# pc_pulse.net
KiCad netlist of a schematic drawn in EAGLE
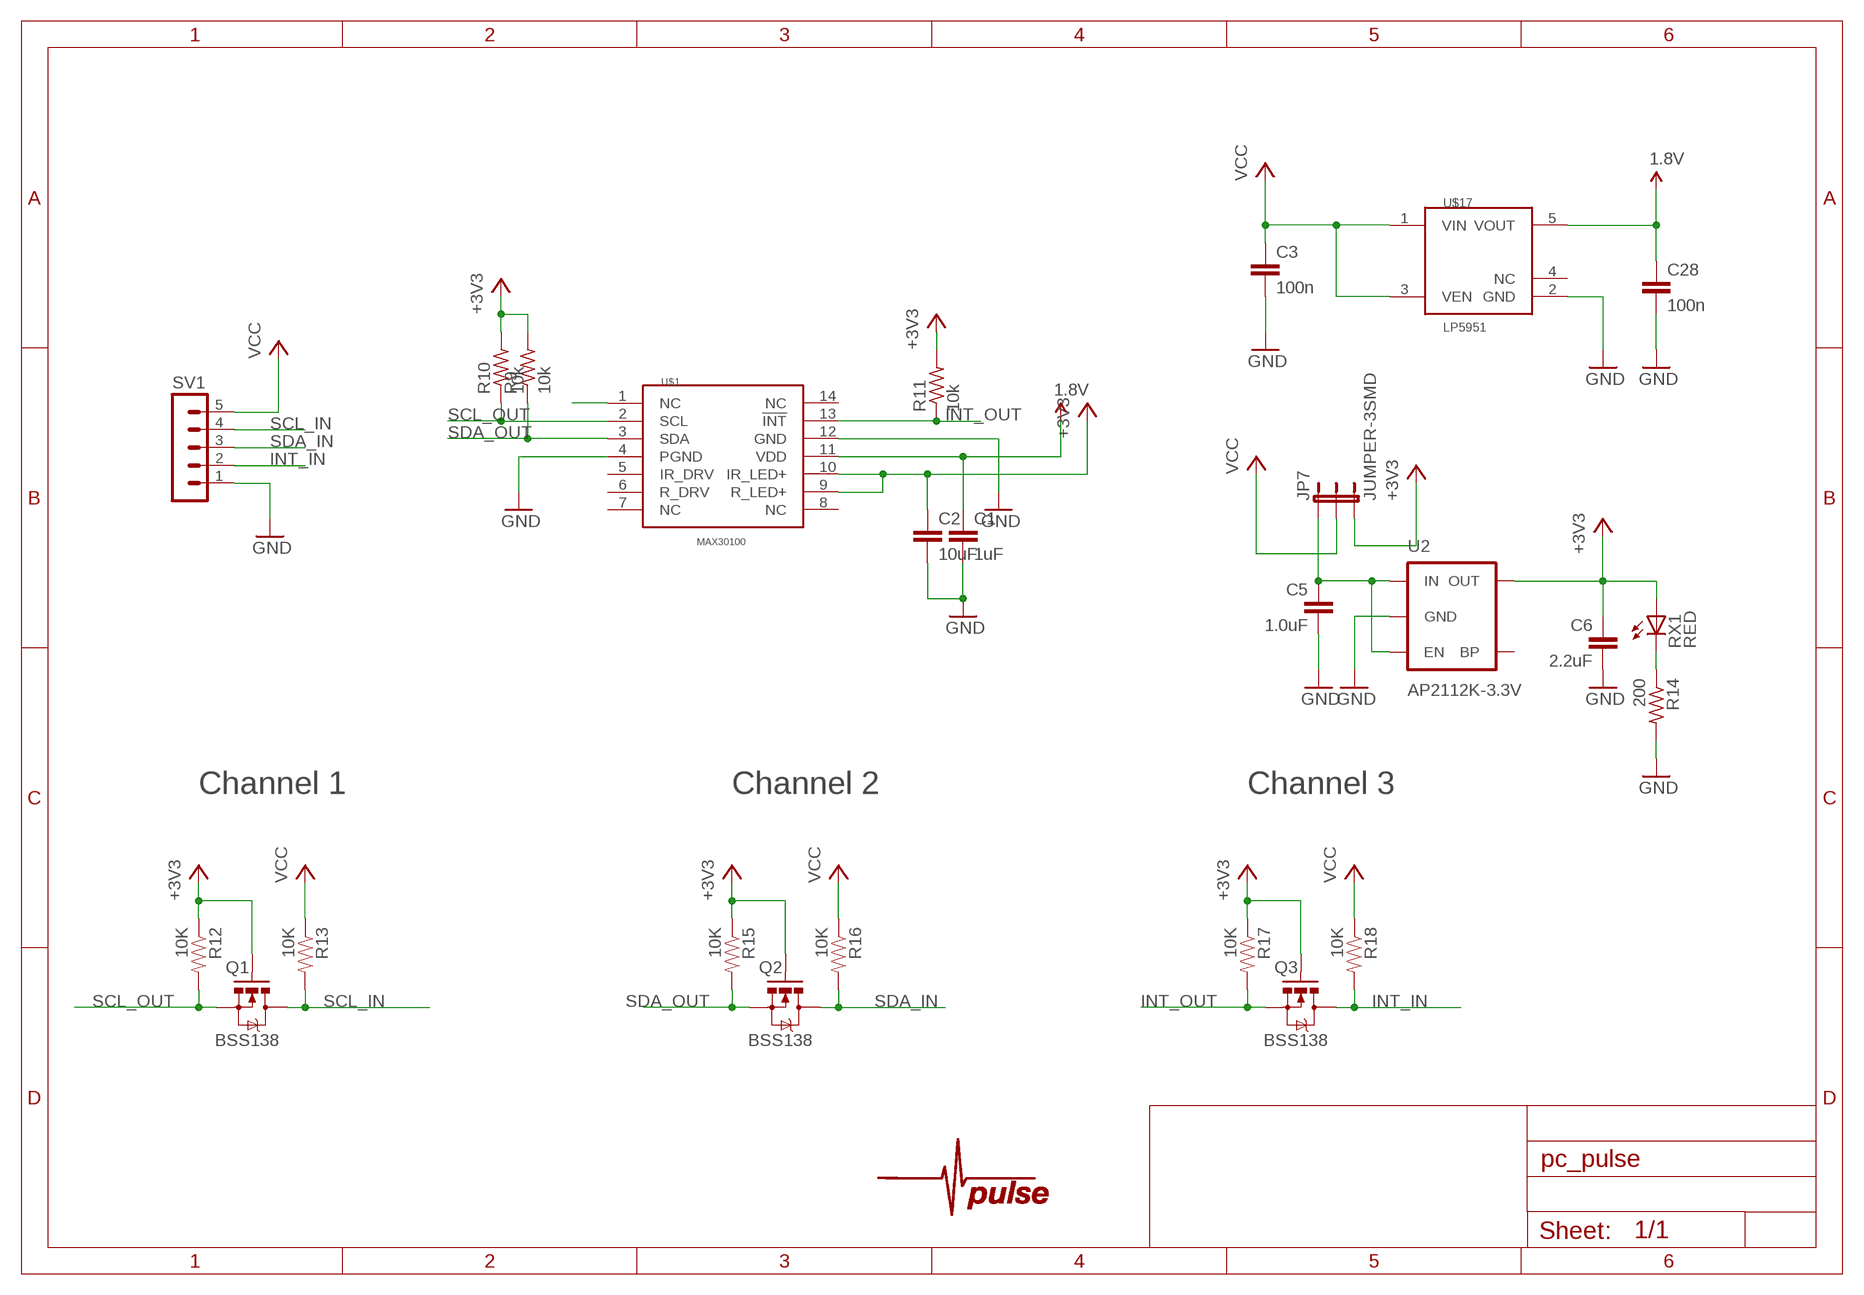
[diagram p0: schematic, sheet 1]

(export (version "E")
  (design (tool "Eeschema 10.0.6"))
  (components
    (comp (ref "C1")
      (value "1uF")
      (footprint "eagle-import:C0805")
      (libsource (lib "eagle-import") (part "C-EUC0805"))
    )
    (comp (ref "C2")
      (value "10uF")
      (footprint "eagle-import:C0805")
      (libsource (lib "eagle-import") (part "C-EUC0805"))
    )
    (comp (ref "C3")
      (value "100n")
      (footprint "eagle-import:C0402")
      (libsource (lib "eagle-import") (part "C-EUC0402"))
    )
    (comp (ref "C5")
      (value "1.0uF")
      (footprint "eagle-import:0805")
      (libsource (lib "eagle-import") (part "1.0UF-25V-+80/-20(0805)"))
    )
    (comp (ref "C6")
      (value "2.2uF")
      (footprint "eagle-import:C0805")
      (libsource (lib "eagle-import") (part "C-EUC0805"))
    )
    (comp (ref "C28")
      (value "100n")
      (footprint "eagle-import:C0402")
      (libsource (lib "eagle-import") (part "C-EUC0402"))
    )
    (comp (ref "JP7")
      (value "JUMPER-3SMD")
      (footprint "eagle-import:SJ_3")
      (libsource (lib "eagle-import") (part "JUMPER-3SMD"))
    )
    (comp (ref "Q1")
      (value "BSS138")
      (footprint "eagle-import:SOT23-3")
      (libsource (lib "eagle-import") (part "MOSFET-NCHANNELSMD"))
    )
    (comp (ref "Q2")
      (value "BSS138")
      (footprint "eagle-import:SOT23-3")
      (libsource (lib "eagle-import") (part "MOSFET-NCHANNELSMD"))
    )
    (comp (ref "Q3")
      (value "BSS138")
      (footprint "eagle-import:SOT23-3")
      (libsource (lib "eagle-import") (part "MOSFET-NCHANNELSMD"))
    )
    (comp (ref "R9")
      (value "10k")
      (footprint "eagle-import:R0402")
      (libsource (lib "eagle-import") (part "R-US_R0402"))
    )
    (comp (ref "R10")
      (value "10k")
      (footprint "eagle-import:R0402")
      (libsource (lib "eagle-import") (part "R-US_R0402"))
    )
    (comp (ref "R11")
      (value "10k")
      (footprint "eagle-import:R0402")
      (libsource (lib "eagle-import") (part "R-US_R0402"))
    )
    (comp (ref "R12")
      (value "10K")
      (footprint "eagle-import:0402-RES")
      (libsource (lib "eagle-import") (part "RESISTOR0402-RES"))
    )
    (comp (ref "R13")
      (value "10K")
      (footprint "eagle-import:0402-RES")
      (libsource (lib "eagle-import") (part "RESISTOR0402-RES"))
    )
    (comp (ref "R14")
      (value "200")
      (footprint "eagle-import:R0402")
      (libsource (lib "eagle-import") (part "R-US_R0402"))
    )
    (comp (ref "R15")
      (value "10K")
      (footprint "eagle-import:0402-RES")
      (libsource (lib "eagle-import") (part "RESISTOR0402-RES"))
    )
    (comp (ref "R16")
      (value "10K")
      (footprint "eagle-import:0402-RES")
      (libsource (lib "eagle-import") (part "RESISTOR0402-RES"))
    )
    (comp (ref "R17")
      (value "10K")
      (footprint "eagle-import:0402-RES")
      (libsource (lib "eagle-import") (part "RESISTOR0402-RES"))
    )
    (comp (ref "R18")
      (value "10K")
      (footprint "eagle-import:0402-RES")
      (libsource (lib "eagle-import") (part "RESISTOR0402-RES"))
    )
    (comp (ref "RX1")
      (value "RED")
      (footprint "eagle-import:CHIPLED_0603")
      (libsource (lib "eagle-import") (part "LEDCHIPLED_0603"))
    )
    (comp (ref "SV1")
      (value "MA05-1")
      (footprint "eagle-import:MA05-1")
      (libsource (lib "eagle-import") (part "MA05-1"))
    )
    (comp (ref "U$1")
      (value "MAX30100")
      (footprint "eagle-import:OESIP-14")
      (libsource (lib "eagle-import") (part "MAX30100"))
    )
    (comp (ref "U$3")
      (value "PROTY_LOGO_WITH_TEXT")
      (footprint "eagle-import:PROTY_WITH_TEXT")
      (libsource (lib "eagle-import") (part "PROTY_LOGO_WITH_TEXT"))
    )
    (comp (ref "U$4")
      (value "PULSE")
      (footprint "eagle-import:PULSE")
      (libsource (lib "eagle-import") (part "PULSE"))
    )
    (comp (ref "U$17")
      (value "LP5951")
      (footprint "eagle-import:SC70-5")
      (libsource (lib "eagle-import") (part "LP5951"))
    )
    (comp (ref "U2")
      (value "AP2112K-3.3V")
      (footprint "eagle-import:SOT23-5")
      (libsource (lib "eagle-import") (part "V_REG_LDOSMD"))
    )
  )
  (nets
    (net (code "1") (name "+3V3") (class "Default")
      (node (ref "C2") (pin "1") (pinfunction "1_1") (pintype "passive"))
      (node (ref "C6") (pin "1") (pinfunction "1_1") (pintype "passive"))
      (node (ref "JP7") (pin "3") (pinfunction "3_3") (pintype "passive"))
      (node (ref "Q1") (pin "1") (pinfunction "G_1") (pintype "passive"))
      (node (ref "Q2") (pin "1") (pinfunction "G_1") (pintype "passive"))
      (node (ref "Q3") (pin "1") (pinfunction "G_1") (pintype "passive"))
      (node (ref "R10") (pin "2") (pinfunction "2_2") (pintype "passive"))
      (node (ref "R11") (pin "2") (pinfunction "2_2") (pintype "passive"))
      (node (ref "R12") (pin "1") (pinfunction "1_1") (pintype "passive"))
      (node (ref "R15") (pin "1") (pinfunction "1_1") (pintype "passive"))
      (node (ref "R17") (pin "1") (pinfunction "1_1") (pintype "passive"))
      (node (ref "R9") (pin "2") (pinfunction "2_2") (pintype "passive"))
      (node (ref "RX1") (pin "A") (pinfunction "A_A") (pintype "passive"))
      (node (ref "U$1") (pin "10") (pinfunction "IR_LED+_10") (pintype "bidirectional"))
      (node (ref "U$1") (pin "9") (pinfunction "R_LED+_9") (pintype "bidirectional"))
      (node (ref "U2") (pin "5") (pinfunction "OUT_5") (pintype "passive"))
    )
    (net (code "2") (name "/INT_IN") (class "Default")
      (node (ref "Q3") (pin "3") (pinfunction "D_3") (pintype "passive"))
      (node (ref "R18") (pin "2") (pinfunction "2_2") (pintype "passive"))
      (node (ref "SV1") (pin "2") (pinfunction "2_2") (pintype "passive"))
    )
    (net (code "3") (name "/INT_OUT") (class "Default")
      (node (ref "Q3") (pin "2") (pinfunction "S_2") (pintype "passive"))
      (node (ref "R11") (pin "1") (pinfunction "1_1") (pintype "passive"))
      (node (ref "R17") (pin "2") (pinfunction "2_2") (pintype "passive"))
      (node (ref "U$1") (pin "13") (pinfunction "~{INT}_13") (pintype "bidirectional"))
    )
    (net (code "4") (name "/SCL_IN") (class "Default")
      (node (ref "Q1") (pin "3") (pinfunction "D_3") (pintype "passive"))
      (node (ref "R13") (pin "2") (pinfunction "2_2") (pintype "passive"))
      (node (ref "SV1") (pin "4") (pinfunction "4_4") (pintype "passive"))
    )
    (net (code "5") (name "/SCL_OUT") (class "Default")
      (node (ref "Q1") (pin "2") (pinfunction "S_2") (pintype "passive"))
      (node (ref "R10") (pin "1") (pinfunction "1_1") (pintype "passive"))
      (node (ref "R12") (pin "2") (pinfunction "2_2") (pintype "passive"))
      (node (ref "U$1") (pin "2") (pinfunction "SCL_2") (pintype "bidirectional"))
    )
    (net (code "6") (name "/SDA_IN") (class "Default")
      (node (ref "Q2") (pin "3") (pinfunction "D_3") (pintype "passive"))
      (node (ref "R16") (pin "2") (pinfunction "2_2") (pintype "passive"))
      (node (ref "SV1") (pin "3") (pinfunction "3_3") (pintype "passive"))
    )
    (net (code "7") (name "/SDA_OUT") (class "Default")
      (node (ref "Q2") (pin "2") (pinfunction "S_2") (pintype "passive"))
      (node (ref "R15") (pin "2") (pinfunction "2_2") (pintype "passive"))
      (node (ref "R9") (pin "1") (pinfunction "1_1") (pintype "passive"))
      (node (ref "U$1") (pin "3") (pinfunction "SDA_3") (pintype "bidirectional"))
    )
    (net (code "8") (name "1.8V") (class "Default")
      (node (ref "C1") (pin "1") (pinfunction "1_1") (pintype "passive"))
      (node (ref "C28") (pin "1") (pinfunction "1_1") (pintype "passive"))
      (node (ref "U$1") (pin "11") (pinfunction "VDD_11") (pintype "bidirectional"))
      (node (ref "U$17") (pin "5") (pinfunction "VOUT_5") (pintype "bidirectional"))
    )
    (net (code "9") (name "GND") (class "Default")
      (node (ref "C1") (pin "2") (pinfunction "2_2") (pintype "passive"))
      (node (ref "C2") (pin "2") (pinfunction "2_2") (pintype "passive"))
      (node (ref "C28") (pin "2") (pinfunction "2_2") (pintype "passive"))
      (node (ref "C3") (pin "2") (pinfunction "2_2") (pintype "passive"))
      (node (ref "C5") (pin "2") (pinfunction "2_2") (pintype "passive"))
      (node (ref "C6") (pin "2") (pinfunction "2_2") (pintype "passive"))
      (node (ref "R14") (pin "2") (pinfunction "2_2") (pintype "passive"))
      (node (ref "SV1") (pin "1") (pinfunction "1_1") (pintype "passive"))
      (node (ref "U$1") (pin "12") (pinfunction "GND_12") (pintype "bidirectional"))
      (node (ref "U$1") (pin "4") (pinfunction "PGND_4") (pintype "bidirectional"))
      (node (ref "U$17") (pin "2") (pinfunction "GND_2") (pintype "bidirectional"))
      (node (ref "U2") (pin "2") (pinfunction "GND_2") (pintype "input"))
    )
    (net (code "10") (name "Net-(R14-Pad1)") (class "Default")
      (node (ref "R14") (pin "1") (pinfunction "1_1") (pintype "passive"))
      (node (ref "RX1") (pin "C") (pinfunction "C_C") (pintype "passive"))
    )
    (net (code "11") (name "Net-(U2-EN)") (class "Default")
      (node (ref "C5") (pin "1") (pinfunction "1_1") (pintype "passive"))
      (node (ref "JP7") (pin "1") (pinfunction "1_1") (pintype "passive"))
      (node (ref "U2") (pin "1") (pinfunction "IN_1") (pintype "input"))
      (node (ref "U2") (pin "3") (pinfunction "EN_3") (pintype "input"))
    )
    (net (code "12") (name "VCC") (class "Default")
      (node (ref "C3") (pin "1") (pinfunction "1_1") (pintype "passive"))
      (node (ref "JP7") (pin "2") (pinfunction "2_2") (pintype "passive"))
      (node (ref "R13") (pin "1") (pinfunction "1_1") (pintype "passive"))
      (node (ref "R16") (pin "1") (pinfunction "1_1") (pintype "passive"))
      (node (ref "R18") (pin "1") (pinfunction "1_1") (pintype "passive"))
      (node (ref "SV1") (pin "5") (pinfunction "5_5") (pintype "passive"))
      (node (ref "U$17") (pin "1") (pinfunction "VIN_1") (pintype "bidirectional"))
      (node (ref "U$17") (pin "3") (pinfunction "VEN_3") (pintype "bidirectional"))
    )
    (net (code "13") (name "unconnected-(U$1-IR_DRV-Pad5)") (class "Default")
      (node (ref "U$1") (pin "5") (pinfunction "IR_DRV_5") (pintype "bidirectional"))
    )
    (net (code "14") (name "unconnected-(U$1-NC-Pad1)") (class "Default")
      (node (ref "U$1") (pin "1") (pinfunction "NC_1") (pintype "bidirectional"))
    )
    (net (code "15") (name "unconnected-(U$1-NC-Pad7)") (class "Default")
      (node (ref "U$1") (pin "7") (pinfunction "NC_7") (pintype "bidirectional"))
    )
    (net (code "16") (name "unconnected-(U$1-NC-Pad8)") (class "Default")
      (node (ref "U$1") (pin "8") (pinfunction "NC_8") (pintype "bidirectional"))
    )
    (net (code "17") (name "unconnected-(U$1-NC-Pad14)") (class "Default")
      (node (ref "U$1") (pin "14") (pinfunction "NC_14") (pintype "bidirectional"))
    )
    (net (code "18") (name "unconnected-(U$1-R_DRV-Pad6)") (class "Default")
      (node (ref "U$1") (pin "6") (pinfunction "R_DRV_6") (pintype "bidirectional"))
    )
    (net (code "19") (name "unconnected-(U$17-NC-Pad4)") (class "Default")
      (node (ref "U$17") (pin "4") (pinfunction "NC_4") (pintype "bidirectional"))
    )
    (net (code "20") (name "unconnected-(U2-BP-Pad4)") (class "Default")
      (node (ref "U2") (pin "4") (pinfunction "BP_4") (pintype "input"))
    )
  )
)
